# Hindi_character1.net
KiCad netlist of a schematic drawn in EAGLE
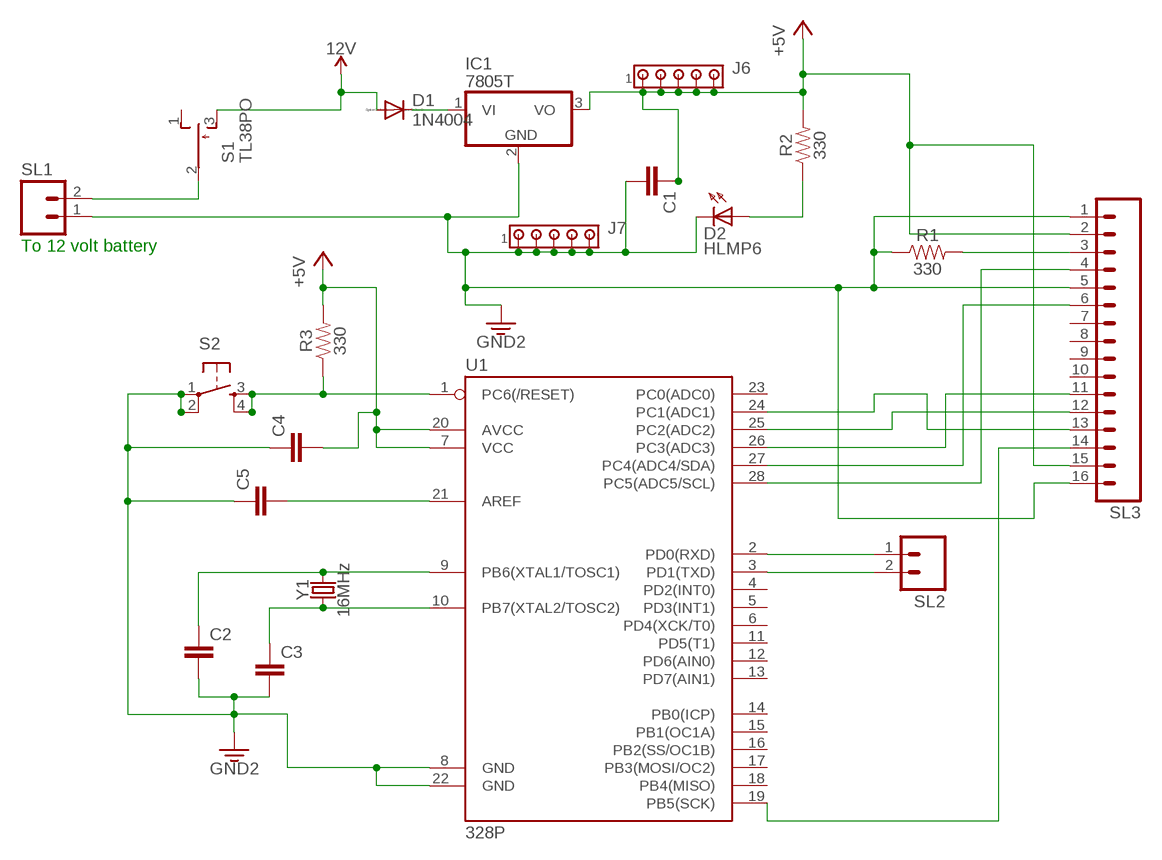
[diagram p0: schematic, sheet 1]

(export (version "E")
  (design (tool "Eeschema 10.0.6"))
  (components
    (comp (ref "C1")
      (value "C5/2.5")
      (footprint "eagle-import:C5B2.5")
      (libsource (lib "eagle-import") (part "C5/2.5"))
    )
    (comp (ref "C2")
      (value "C5/2.5")
      (footprint "eagle-import:C5B2.5")
      (libsource (lib "eagle-import") (part "C5/2.5"))
    )
    (comp (ref "C3")
      (value "C5/2.5")
      (footprint "eagle-import:C5B2.5")
      (libsource (lib "eagle-import") (part "C5/2.5"))
    )
    (comp (ref "C4")
      (value "C5/2.5")
      (footprint "eagle-import:C5B2.5")
      (libsource (lib "eagle-import") (part "C5/2.5"))
    )
    (comp (ref "C5")
      (value "C5/2.5")
      (footprint "eagle-import:C5B2.5")
      (libsource (lib "eagle-import") (part "C5/2.5"))
    )
    (comp (ref "D1")
      (value "1N4004")
      (footprint "eagle-import:DO41-10")
      (libsource (lib "eagle-import") (part "1N4004"))
    )
    (comp (ref "D2")
      (value "HLMP6")
      (footprint "eagle-import:HLMP6")
      (fields (field (name "MF") "AGILENT TECHNOLOGIES") (field (name "MPN") "HLMP-6500"))
      (libsource (lib "eagle-import") (part "HLMP6"))
    )
    (comp (ref "IC1")
      (value "7805T")
      (footprint "eagle-import:TO220H")
      (libsource (lib "eagle-import") (part "78T05"))
    )
    (comp (ref "J6")
      (value "MTA05-100")
      (footprint "eagle-import:10X05MTA")
      (libsource (lib "eagle-import") (part "MTA05-100"))
    )
    (comp (ref "J7")
      (value "MTA05-100")
      (footprint "eagle-import:10X05MTA")
      (libsource (lib "eagle-import") (part "MTA05-100"))
    )
    (comp (ref "R1")
      (value "330")
      (footprint "eagle-import:AXIAL-0.3")
      (libsource (lib "eagle-import") (part "330OHM-HORIZ-1/10W-5%"))
    )
    (comp (ref "R2")
      (value "330")
      (footprint "eagle-import:AXIAL-0.3")
      (libsource (lib "eagle-import") (part "330OHM-HORIZ-1/10W-5%"))
    )
    (comp (ref "R3")
      (value "330")
      (footprint "eagle-import:AXIAL-0.3")
      (libsource (lib "eagle-import") (part "330OHM-HORIZ-1/10W-5%"))
    )
    (comp (ref "S1")
      (value "TL38PO")
      (footprint "eagle-import:TL3XPO")
      (libsource (lib "eagle-import") (part "TL38PO"))
    )
    (comp (ref "S2")
      (value "TAC_SWITCHPTH")
      (footprint "eagle-import:TACTILE-PTH")
      (libsource (lib "eagle-import") (part "TAC_SWITCHPTH"))
    )
    (comp (ref "SL1")
      (value "MA02")
      (footprint "eagle-import:02PA")
      (libsource (lib "eagle-import") (part "MA02"))
    )
    (comp (ref "SL2")
      (value "MA02")
      (footprint "eagle-import:02PA")
      (libsource (lib "eagle-import") (part "MA02"))
    )
    (comp (ref "SL3")
      (value "MA16")
      (footprint "eagle-import:16PA")
      (libsource (lib "eagle-import") (part "MA16"))
    )
    (comp (ref "U1")
      (value "328P")
      (footprint "eagle-import:DIP28")
      (libsource (lib "eagle-import") (part "ATMEGA328P_PDIP"))
    )
    (comp (ref "Y1")
      (value "16MHz")
      (footprint "eagle-import:HC49US")
      (libsource (lib "eagle-import") (part "CRYSTAL-16MHZPTH-HC49US"))
    )
  )
  (nets
    (net (code "1") (name "+5V") (class "Default")
      (node (ref "C1") (pin "1") (pinfunction "1_1") (pintype "passive"))
      (node (ref "C4") (pin "2") (pinfunction "2_2") (pintype "passive"))
      (node (ref "IC1") (pin "3") (pinfunction "VO_3") (pintype "passive"))
      (node (ref "J6") (pin "1") (pinfunction "1_1") (pintype "passive"))
      (node (ref "J6") (pin "2") (pinfunction "2_2") (pintype "passive"))
      (node (ref "J6") (pin "3") (pinfunction "3_3") (pintype "passive"))
      (node (ref "J6") (pin "4") (pinfunction "4_4") (pintype "passive"))
      (node (ref "J6") (pin "5") (pinfunction "5_5") (pintype "passive"))
      (node (ref "R2") (pin "P$2") (pinfunction "2_P$2") (pintype "passive"))
      (node (ref "R3") (pin "P$2") (pinfunction "2_P$2") (pintype "passive"))
      (node (ref "SL3") (pin "15") (pinfunction "15_15") (pintype "passive"))
      (node (ref "SL3") (pin "2") (pinfunction "2_2") (pintype "passive"))
      (node (ref "U1") (pin "20") (pinfunction "AVCC_20") (pintype "bidirectional"))
      (node (ref "U1") (pin "7") (pinfunction "VCC_7") (pintype "bidirectional"))
    )
    (net (code "2") (name "12V") (class "Default")
      (node (ref "D1") (pin "A") (pinfunction "A_A") (pintype "passive"))
      (node (ref "S1") (pin "3") (pinfunction "S_3") (pintype "passive"))
    )
    (net (code "3") (name "GND2") (class "Default")
      (node (ref "C1") (pin "2") (pinfunction "2_2") (pintype "passive"))
      (node (ref "C2") (pin "2") (pinfunction "2_2") (pintype "passive"))
      (node (ref "C3") (pin "2") (pinfunction "2_2") (pintype "passive"))
      (node (ref "C4") (pin "1") (pinfunction "1_1") (pintype "passive"))
      (node (ref "C5") (pin "1") (pinfunction "1_1") (pintype "passive"))
      (node (ref "D2") (pin "K") (pinfunction "K_K") (pintype "passive"))
      (node (ref "IC1") (pin "2") (pinfunction "GND_2") (pintype "passive"))
      (node (ref "J7") (pin "1") (pinfunction "1_1") (pintype "passive"))
      (node (ref "J7") (pin "2") (pinfunction "2_2") (pintype "passive"))
      (node (ref "J7") (pin "3") (pinfunction "3_3") (pintype "passive"))
      (node (ref "J7") (pin "4") (pinfunction "4_4") (pintype "passive"))
      (node (ref "J7") (pin "5") (pinfunction "5_5") (pintype "passive"))
      (node (ref "R1") (pin "P$1") (pinfunction "1_P$1") (pintype "passive"))
      (node (ref "S2") (pin "1") (pinfunction "1_1") (pintype "passive"))
      (node (ref "S2") (pin "2") (pinfunction "2_2") (pintype "passive"))
      (node (ref "SL1") (pin "1") (pinfunction "1_1") (pintype "passive"))
      (node (ref "SL3") (pin "1") (pinfunction "1_1") (pintype "passive"))
      (node (ref "SL3") (pin "16") (pinfunction "16_16") (pintype "passive"))
      (node (ref "SL3") (pin "5") (pinfunction "5_5") (pintype "passive"))
      (node (ref "U1") (pin "22") (pinfunction "GND_22") (pintype "bidirectional"))
      (node (ref "U1") (pin "8") (pinfunction "GND_8") (pintype "bidirectional"))
    )
    (net (code "4") (name "Net-(IC1-VI)") (class "Default")
      (node (ref "D1") (pin "C") (pinfunction "C_C") (pintype "passive"))
      (node (ref "IC1") (pin "1") (pinfunction "VI_1") (pintype "input"))
    )
    (net (code "5") (name "Net-(R1-2)") (class "Default")
      (node (ref "R1") (pin "P$2") (pinfunction "2_P$2") (pintype "passive"))
      (node (ref "SL3") (pin "3") (pinfunction "3_3") (pintype "passive"))
    )
    (net (code "6") (name "Net-(R2-1)") (class "Default")
      (node (ref "D2") (pin "A") (pinfunction "A_A") (pintype "passive"))
      (node (ref "R2") (pin "P$1") (pinfunction "1_P$1") (pintype "passive"))
    )
    (net (code "7") (name "Net-(R3-1)") (class "Default")
      (node (ref "R3") (pin "P$1") (pinfunction "1_P$1") (pintype "passive"))
      (node (ref "S2") (pin "3") (pinfunction "3_3") (pintype "passive"))
      (node (ref "S2") (pin "4") (pinfunction "4_4") (pintype "passive"))
      (node (ref "U1") (pin "1") (pinfunction "PC6(/RESET)_1") (pintype "bidirectional"))
    )
    (net (code "8") (name "Net-(S1-P)") (class "Default")
      (node (ref "S1") (pin "2") (pinfunction "P_2") (pintype "passive"))
      (node (ref "SL1") (pin "2") (pinfunction "2_2") (pintype "passive"))
    )
    (net (code "9") (name "Net-(U1-AREF)") (class "Default")
      (node (ref "C5") (pin "2") (pinfunction "2_2") (pintype "passive"))
      (node (ref "U1") (pin "21") (pinfunction "AREF_21") (pintype "bidirectional"))
    )
    (net (code "10") (name "Net-(U1-PB5(SCK))") (class "Default")
      (node (ref "SL3") (pin "14") (pinfunction "14_14") (pintype "passive"))
      (node (ref "U1") (pin "19") (pinfunction "PB5(SCK)_19") (pintype "bidirectional"))
    )
    (net (code "11") (name "Net-(U1-PB6(XTAL1{slash}TOSC1))") (class "Default")
      (node (ref "C2") (pin "1") (pinfunction "1_1") (pintype "passive"))
      (node (ref "U1") (pin "9") (pinfunction "PB6(XTAL1/TOSC1)_9") (pintype "bidirectional"))
      (node (ref "Y1") (pin "2") (pinfunction "2_2") (pintype "passive"))
    )
    (net (code "12") (name "Net-(U1-PB7(XTAL2{slash}TOSC2))") (class "Default")
      (node (ref "C3") (pin "1") (pinfunction "1_1") (pintype "passive"))
      (node (ref "U1") (pin "10") (pinfunction "PB7(XTAL2/TOSC2)_10") (pintype "bidirectional"))
      (node (ref "Y1") (pin "1") (pinfunction "1_1") (pintype "passive"))
    )
    (net (code "13") (name "Net-(U1-PC1(ADC1))") (class "Default")
      (node (ref "SL3") (pin "13") (pinfunction "13_13") (pintype "passive"))
      (node (ref "U1") (pin "24") (pinfunction "PC1(ADC1)_24") (pintype "bidirectional"))
    )
    (net (code "14") (name "Net-(U1-PC2(ADC2))") (class "Default")
      (node (ref "SL3") (pin "12") (pinfunction "12_12") (pintype "passive"))
      (node (ref "U1") (pin "25") (pinfunction "PC2(ADC2)_25") (pintype "bidirectional"))
    )
    (net (code "15") (name "Net-(U1-PC3(ADC3))") (class "Default")
      (node (ref "SL3") (pin "11") (pinfunction "11_11") (pintype "passive"))
      (node (ref "U1") (pin "26") (pinfunction "PC3(ADC3)_26") (pintype "bidirectional"))
    )
    (net (code "16") (name "Net-(U1-PC4(ADC4{slash}SDA))") (class "Default")
      (node (ref "SL3") (pin "6") (pinfunction "6_6") (pintype "passive"))
      (node (ref "U1") (pin "27") (pinfunction "PC4(ADC4/SDA)_27") (pintype "bidirectional"))
    )
    (net (code "17") (name "Net-(U1-PC5(ADC5{slash}SCL))") (class "Default")
      (node (ref "SL3") (pin "4") (pinfunction "4_4") (pintype "passive"))
      (node (ref "U1") (pin "28") (pinfunction "PC5(ADC5/SCL)_28") (pintype "bidirectional"))
    )
    (net (code "18") (name "Net-(U1-PD0(RXD))") (class "Default")
      (node (ref "SL2") (pin "1") (pinfunction "1_1") (pintype "passive"))
      (node (ref "U1") (pin "2") (pinfunction "PD0(RXD)_2") (pintype "bidirectional"))
    )
    (net (code "19") (name "Net-(U1-PD1(TXD))") (class "Default")
      (node (ref "SL2") (pin "2") (pinfunction "2_2") (pintype "passive"))
      (node (ref "U1") (pin "3") (pinfunction "PD1(TXD)_3") (pintype "bidirectional"))
    )
    (net (code "20") (name "unconnected-(S1-O-Pad1)") (class "Default")
      (node (ref "S1") (pin "1") (pinfunction "O_1") (pintype "passive"))
    )
    (net (code "21") (name "unconnected-(SL3-Pad7)") (class "Default")
      (node (ref "SL3") (pin "7") (pinfunction "7_7") (pintype "passive"))
    )
    (net (code "22") (name "unconnected-(SL3-Pad8)") (class "Default")
      (node (ref "SL3") (pin "8") (pinfunction "8_8") (pintype "passive"))
    )
    (net (code "23") (name "unconnected-(SL3-Pad9)") (class "Default")
      (node (ref "SL3") (pin "9") (pinfunction "9_9") (pintype "passive"))
    )
    (net (code "24") (name "unconnected-(SL3-Pad10)") (class "Default")
      (node (ref "SL3") (pin "10") (pinfunction "10_10") (pintype "passive"))
    )
    (net (code "25") (name "unconnected-(U1-PB0(ICP)-Pad14)") (class "Default")
      (node (ref "U1") (pin "14") (pinfunction "PB0(ICP)_14") (pintype "bidirectional"))
    )
    (net (code "26") (name "unconnected-(U1-PB1(OC1A)-Pad15)") (class "Default")
      (node (ref "U1") (pin "15") (pinfunction "PB1(OC1A)_15") (pintype "bidirectional"))
    )
    (net (code "27") (name "unconnected-(U1-PB2(SS{slash}OC1B)-Pad16)") (class "Default")
      (node (ref "U1") (pin "16") (pinfunction "PB2(SS/OC1B)_16") (pintype "bidirectional"))
    )
    (net (code "28") (name "unconnected-(U1-PB3(MOSI{slash}OC2)-Pad17)") (class "Default")
      (node (ref "U1") (pin "17") (pinfunction "PB3(MOSI/OC2)_17") (pintype "bidirectional"))
    )
    (net (code "29") (name "unconnected-(U1-PB4(MISO)-Pad18)") (class "Default")
      (node (ref "U1") (pin "18") (pinfunction "PB4(MISO)_18") (pintype "bidirectional"))
    )
    (net (code "30") (name "unconnected-(U1-PC0(ADC0)-Pad23)") (class "Default")
      (node (ref "U1") (pin "23") (pinfunction "PC0(ADC0)_23") (pintype "bidirectional"))
    )
    (net (code "31") (name "unconnected-(U1-PD2(INT0)-Pad4)") (class "Default")
      (node (ref "U1") (pin "4") (pinfunction "PD2(INT0)_4") (pintype "bidirectional"))
    )
    (net (code "32") (name "unconnected-(U1-PD3(INT1)-Pad5)") (class "Default")
      (node (ref "U1") (pin "5") (pinfunction "PD3(INT1)_5") (pintype "bidirectional"))
    )
    (net (code "33") (name "unconnected-(U1-PD4(XCK{slash}T0)-Pad6)") (class "Default")
      (node (ref "U1") (pin "6") (pinfunction "PD4(XCK/T0)_6") (pintype "bidirectional"))
    )
    (net (code "34") (name "unconnected-(U1-PD5(T1)-Pad11)") (class "Default")
      (node (ref "U1") (pin "11") (pinfunction "PD5(T1)_11") (pintype "bidirectional"))
    )
    (net (code "35") (name "unconnected-(U1-PD6(AIN0)-Pad12)") (class "Default")
      (node (ref "U1") (pin "12") (pinfunction "PD6(AIN0)_12") (pintype "bidirectional"))
    )
    (net (code "36") (name "unconnected-(U1-PD7(AIN1)-Pad13)") (class "Default")
      (node (ref "U1") (pin "13") (pinfunction "PD7(AIN1)_13") (pintype "bidirectional"))
    )
  )
)
